# TopLevelSchem.net
KiCad netlist of a schematic drawn in Altium Designer
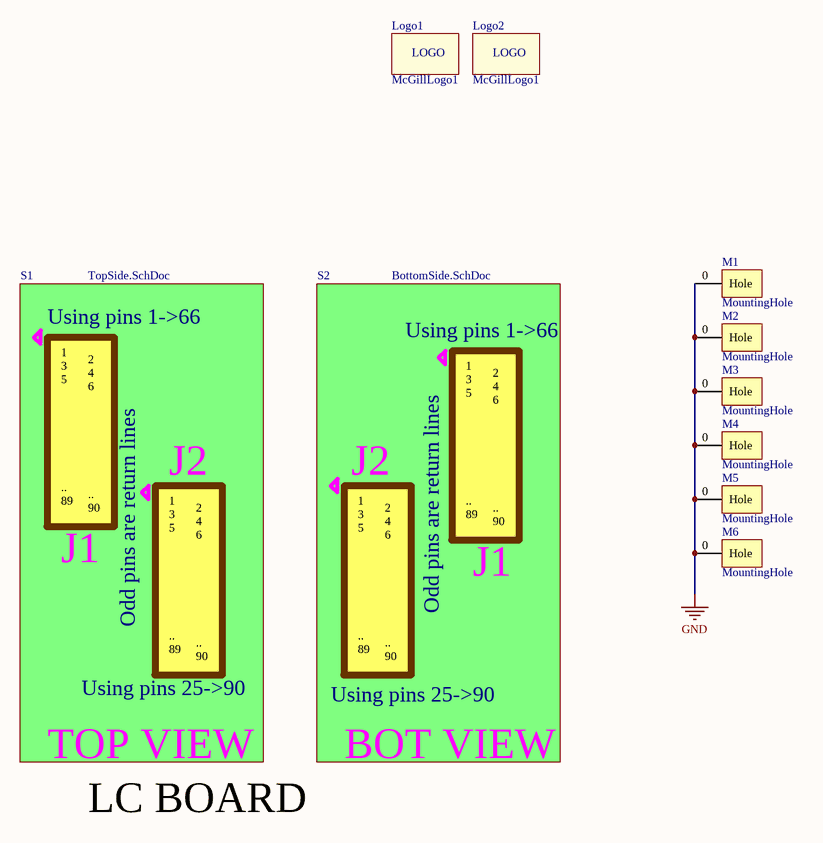
[diagram p0: TopLevelSchem.SchDoc]

(export (version "E")
  (design (tool "Eeschema 10.0.6"))
  (components
    (comp (ref "Logo1")
      (value "McGillLogo1")
      (footprint "McGillLogo1")
      (libsource (lib "SPT3G_LCBoard") (part "Logo"))
    )
    (comp (ref "Logo2")
      (value "McGillLogo1")
      (footprint "McGillLogo1")
      (libsource (lib "SPT3G_LCBoard") (part "Logo"))
    )
    (comp (ref "M1")
      (value "MountingHole")
      (footprint "MountingHole")
      (libsource (lib "SPT3G_LCBoard") (part "MountingHole"))
    )
    (comp (ref "M2")
      (value "MountingHole")
      (footprint "MountingHole")
      (libsource (lib "SPT3G_LCBoard") (part "MountingHole"))
    )
    (comp (ref "M3")
      (value "MountingHole")
      (footprint "MountingHole")
      (libsource (lib "SPT3G_LCBoard") (part "MountingHole"))
    )
    (comp (ref "M4")
      (value "MountingHole")
      (footprint "MountingHole")
      (libsource (lib "SPT3G_LCBoard") (part "MountingHole"))
    )
    (comp (ref "M5")
      (value "MountingHole")
      (footprint "MountingHole")
      (libsource (lib "SPT3G_LCBoard") (part "MountingHole"))
    )
    (comp (ref "M6")
      (value "MountingHole")
      (footprint "MountingHole")
      (libsource (lib "SPT3G_LCBoard") (part "MountingHole"))
    )
  )
  (nets
    (net (code "1") (name "GND") (class "Default")
      (node (ref "M1") (pin "0") (pinfunction "Hole_0") (pintype "passive"))
      (node (ref "M2") (pin "0") (pinfunction "Hole_0") (pintype "passive"))
      (node (ref "M3") (pin "0") (pinfunction "Hole_0") (pintype "passive"))
      (node (ref "M4") (pin "0") (pinfunction "Hole_0") (pintype "passive"))
      (node (ref "M5") (pin "0") (pinfunction "Hole_0") (pintype "passive"))
      (node (ref "M6") (pin "0") (pinfunction "Hole_0") (pintype "passive"))
    )
  )
)
